# Modules.net
KiCad netlist of a schematic drawn in Altium Designer
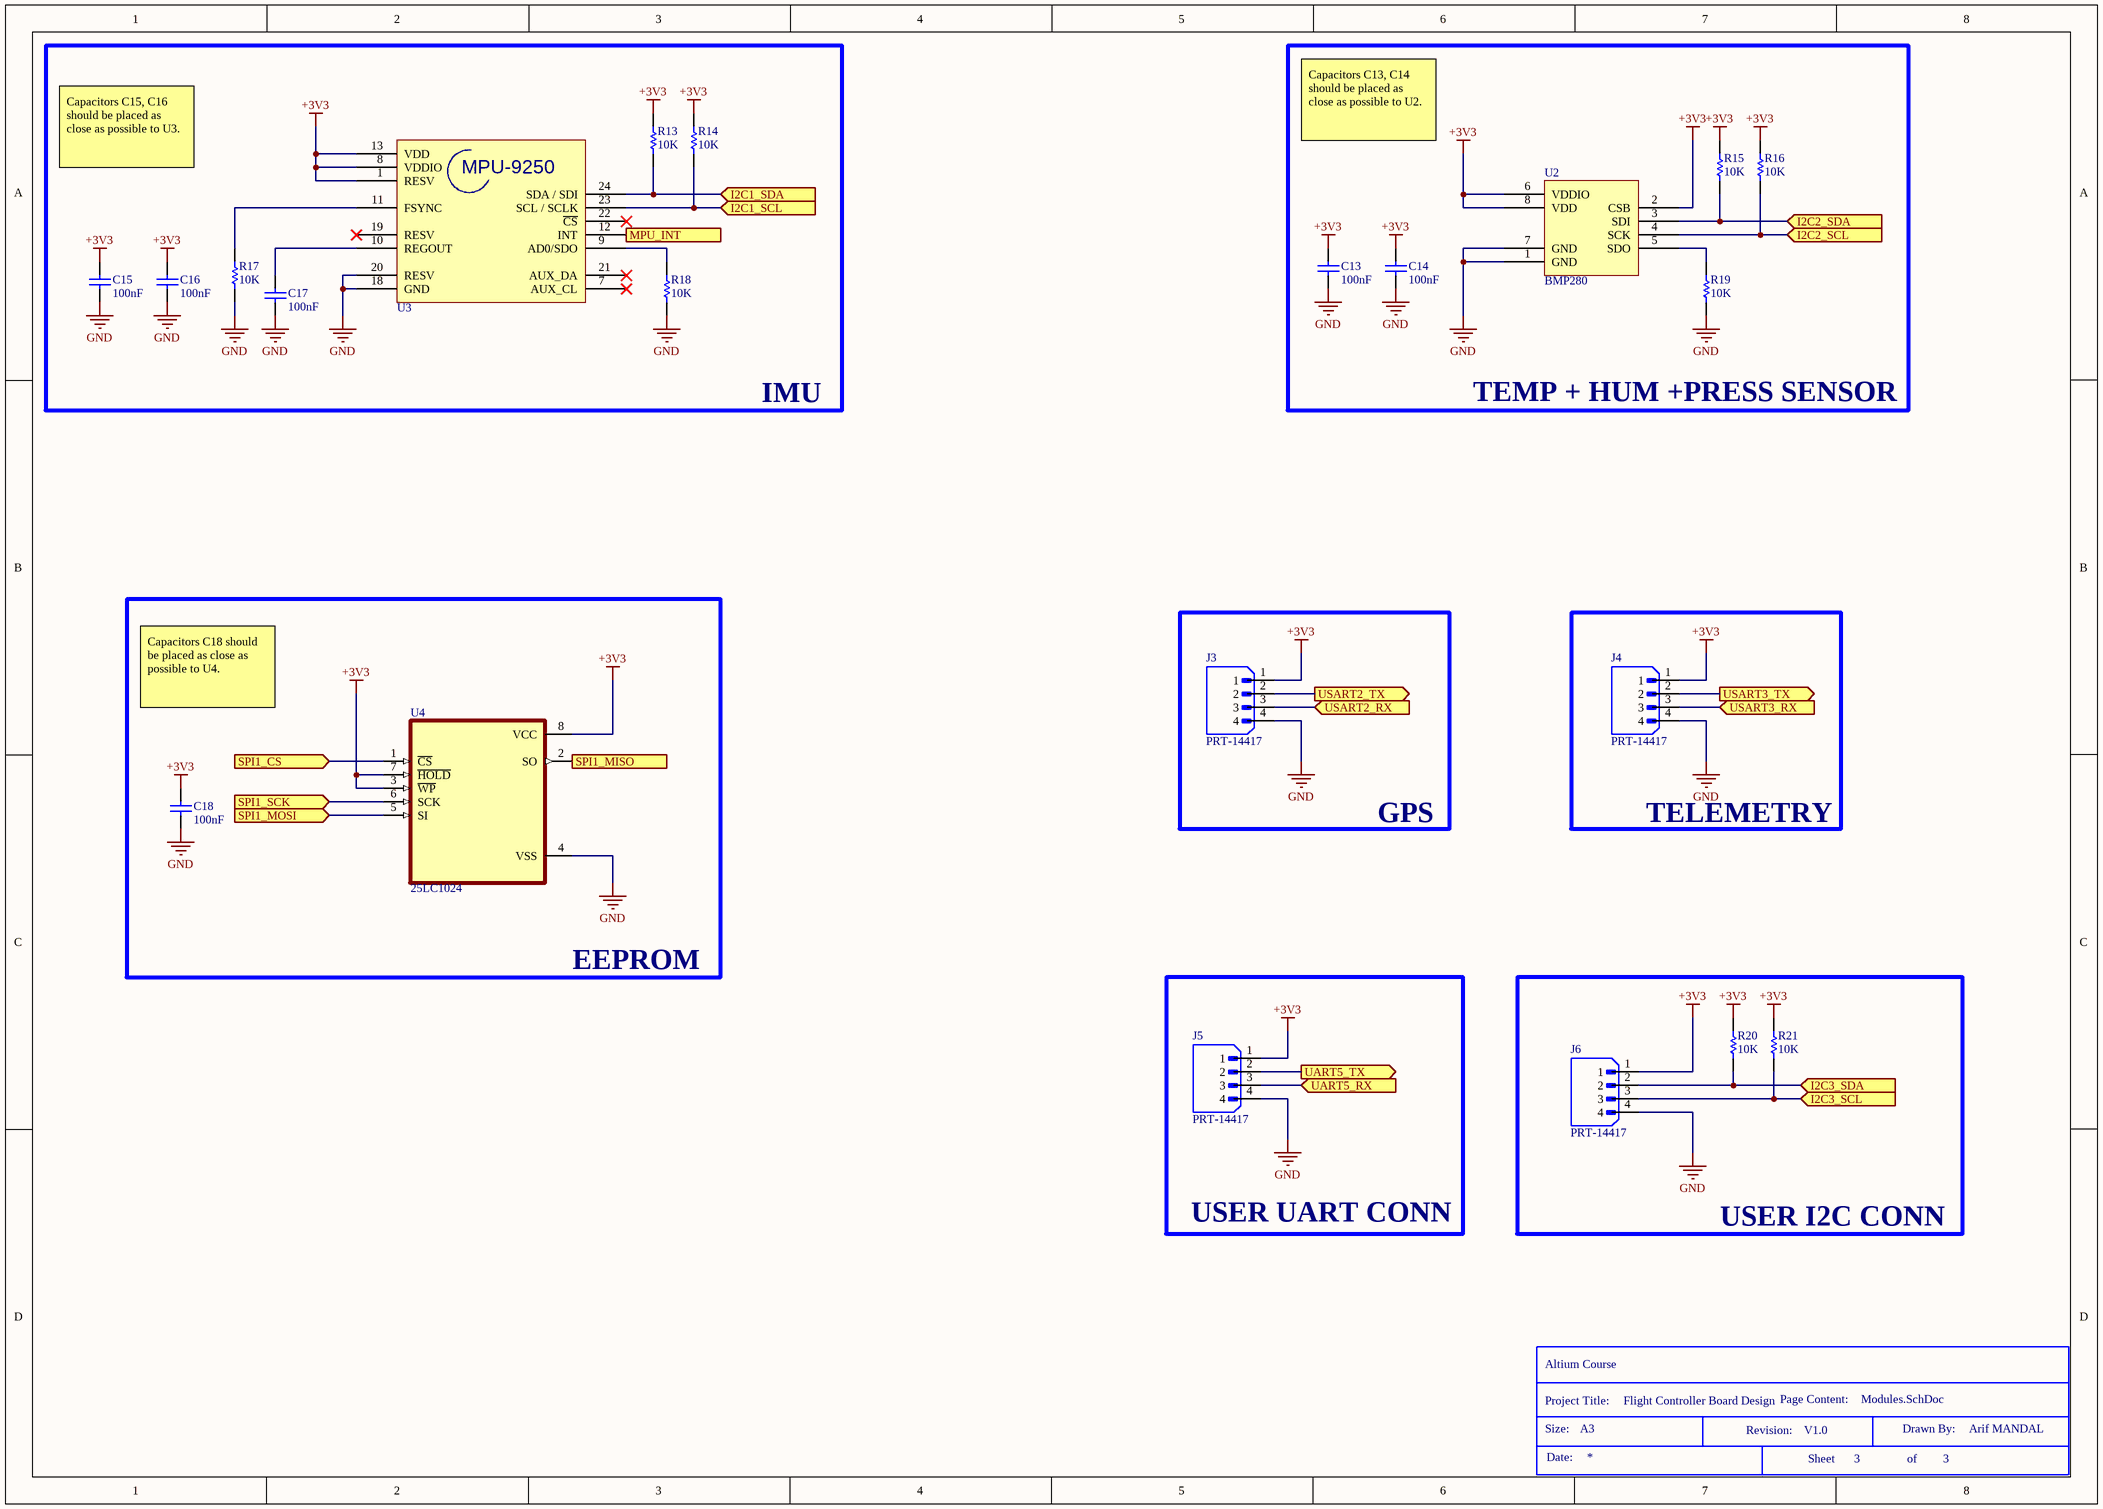
[diagram p0: Modules.SchDoc]

(export (version "E")
  (design (tool "Eeschema 10.0.6"))
  (components
    (comp (ref "C13")
      (value "100nF")
      (footprint "C805")
      (description "Capacitor")
      (fields (field (name "DESIGNER") "Parsa Malekpour"))
      (libsource (lib "ParsaLibrary") (part "Cap"))
    )
    (comp (ref "C14")
      (value "100nF")
      (footprint "C805")
      (description "Capacitor")
      (fields (field (name "DESIGNER") "Parsa Malekpour"))
      (libsource (lib "ParsaLibrary") (part "Cap"))
    )
    (comp (ref "C15")
      (value "100nF")
      (footprint "C805")
      (description "Capacitor")
      (fields (field (name "DESIGNER") "Parsa Malekpour"))
      (libsource (lib "ParsaLibrary") (part "Cap"))
    )
    (comp (ref "C16")
      (value "100nF")
      (footprint "C805")
      (description "Capacitor")
      (fields (field (name "DESIGNER") "Parsa Malekpour"))
      (libsource (lib "ParsaLibrary") (part "Cap"))
    )
    (comp (ref "C17")
      (value "100nF")
      (footprint "C805")
      (description "Capacitor")
      (fields (field (name "DESIGNER") "Parsa Malekpour"))
      (libsource (lib "ParsaLibrary") (part "Cap"))
    )
    (comp (ref "C18")
      (value "100nF")
      (footprint "C805")
      (description "Capacitor")
      (fields (field (name "DESIGNER") "Parsa Malekpour"))
      (libsource (lib "ParsaLibrary") (part "Cap"))
    )
    (comp (ref "J3")
      (value "PRT-14417")
      (footprint "SPARKFUN_PRT-14417")
      (description "QWIIC JST CONNECTOR - SMD 4-PIN")
      (fields (field (name "MF") "SparkFun Electronics"))
      (libsource (lib "Flight_Controller_Board_Design") (part "PRT-14417"))
    )
    (comp (ref "J4")
      (value "PRT-14417")
      (footprint "SPARKFUN_PRT-14417")
      (description "QWIIC JST CONNECTOR - SMD 4-PIN")
      (fields (field (name "MF") "SparkFun Electronics"))
      (libsource (lib "Flight_Controller_Board_Design") (part "PRT-14417"))
    )
    (comp (ref "J5")
      (value "PRT-14417")
      (footprint "SPARKFUN_PRT-14417")
      (description "QWIIC JST CONNECTOR - SMD 4-PIN")
      (fields (field (name "MF") "SparkFun Electronics"))
      (libsource (lib "Flight_Controller_Board_Design") (part "PRT-14417"))
    )
    (comp (ref "J6")
      (value "PRT-14417")
      (footprint "SPARKFUN_PRT-14417")
      (description "QWIIC JST CONNECTOR - SMD 4-PIN")
      (fields (field (name "MF") "SparkFun Electronics"))
      (libsource (lib "Flight_Controller_Board_Design") (part "PRT-14417"))
    )
    (comp (ref "R13")
      (value "10K")
      (footprint "R805")
      (description "Resistor")
      (fields (field (name "DESIGNER") "Parsa Malekpour"))
      (libsource (lib "ParsaLibrary") (part "Resistor"))
    )
    (comp (ref "R14")
      (value "10K")
      (footprint "R805")
      (description "Resistor")
      (fields (field (name "DESIGNER") "Parsa Malekpour"))
      (libsource (lib "ParsaLibrary") (part "Resistor"))
    )
    (comp (ref "R15")
      (value "10K")
      (footprint "R805")
      (description "Resistor")
      (fields (field (name "DESIGNER") "Parsa Malekpour"))
      (libsource (lib "ParsaLibrary") (part "Resistor"))
    )
    (comp (ref "R16")
      (value "10K")
      (footprint "R805")
      (description "Resistor")
      (fields (field (name "DESIGNER") "Parsa Malekpour"))
      (libsource (lib "ParsaLibrary") (part "Resistor"))
    )
    (comp (ref "R17")
      (value "10K")
      (footprint "R805")
      (description "Resistor")
      (fields (field (name "DESIGNER") "Parsa Malekpour"))
      (libsource (lib "ParsaLibrary") (part "Resistor"))
    )
    (comp (ref "R18")
      (value "10K")
      (footprint "R805")
      (description "Resistor")
      (fields (field (name "DESIGNER") "Parsa Malekpour"))
      (libsource (lib "ParsaLibrary") (part "Resistor"))
    )
    (comp (ref "R19")
      (value "10K")
      (footprint "R805")
      (description "Resistor")
      (fields (field (name "DESIGNER") "Parsa Malekpour"))
      (libsource (lib "ParsaLibrary") (part "Resistor"))
    )
    (comp (ref "R20")
      (value "10K")
      (footprint "R805")
      (description "Resistor")
      (fields (field (name "DESIGNER") "Parsa Malekpour"))
      (libsource (lib "ParsaLibrary") (part "Resistor"))
    )
    (comp (ref "R21")
      (value "10K")
      (footprint "R805")
      (description "Resistor")
      (fields (field (name "DESIGNER") "Parsa Malekpour"))
      (libsource (lib "ParsaLibrary") (part "Resistor"))
    )
    (comp (ref "U2")
      (value "BMP280")
      (footprint "BMP280")
      (description "Digital Pressure Sensor")
      (libsource (lib "ParsaLibrary") (part "BMP280"))
    )
    (comp (ref "U3")
      (value "MPU-9250")
      (footprint "QFN-24")
      (libsource (lib "ParsaLibrary") (part "MPU-9250"))
    )
    (comp (ref "U4")
      (value "25LC1024")
      (footprint "SOIC-8N")
      (description "EEPROM Memory IC 1Mb _128K x 8_ SPI 20MHz 8-SOIJ")
      (fields (field (name "MP") "25LC1024-I/SM") (field (name "MF") "Microchip"))
      (libsource (lib "Flight_Controller_Board_Design") (part "25LC1024"))
    )
  )
  (nets
    (net (code "1") (name "+3V3") (class "Default")
      (node (ref "C13") (pin "2") (pinfunction "2_2") (pintype "passive"))
      (node (ref "C14") (pin "2") (pinfunction "2_2") (pintype "passive"))
      (node (ref "C15") (pin "2") (pinfunction "2_2") (pintype "passive"))
      (node (ref "C16") (pin "2") (pinfunction "2_2") (pintype "passive"))
      (node (ref "C18") (pin "2") (pinfunction "2_2") (pintype "passive"))
      (node (ref "J3") (pin "1") (pinfunction "1_1") (pintype "passive"))
      (node (ref "J4") (pin "1") (pinfunction "1_1") (pintype "passive"))
      (node (ref "J5") (pin "1") (pinfunction "1_1") (pintype "passive"))
      (node (ref "J6") (pin "1") (pinfunction "1_1") (pintype "passive"))
      (node (ref "R13") (pin "2") (pinfunction "2_2") (pintype "passive"))
      (node (ref "R14") (pin "2") (pinfunction "2_2") (pintype "passive"))
      (node (ref "R15") (pin "2") (pinfunction "2_2") (pintype "passive"))
      (node (ref "R16") (pin "2") (pinfunction "2_2") (pintype "passive"))
      (node (ref "R20") (pin "2") (pinfunction "2_2") (pintype "passive"))
      (node (ref "R21") (pin "2") (pinfunction "2_2") (pintype "passive"))
      (node (ref "U2") (pin "2") (pinfunction "CSB_2") (pintype "passive"))
      (node (ref "U2") (pin "6") (pinfunction "VDDIO_6") (pintype "passive"))
      (node (ref "U2") (pin "8") (pinfunction "VDD_8") (pintype "passive"))
      (node (ref "U3") (pin "1") (pinfunction "RESV_1") (pintype "passive"))
      (node (ref "U3") (pin "13") (pinfunction "VDD_13") (pintype "passive"))
      (node (ref "U3") (pin "8") (pinfunction "VDDIO_8") (pintype "passive"))
      (node (ref "U4") (pin "3") (pinfunction "~{WP}_3") (pintype "input"))
      (node (ref "U4") (pin "7") (pinfunction "~{HOLD}_7") (pintype "input"))
      (node (ref "U4") (pin "8") (pinfunction "VCC_8") (pintype "power_in"))
    )
    (net (code "2") (name "/I2C1_SCL") (class "Default")
      (node (ref "R14") (pin "1") (pinfunction "1_1") (pintype "passive"))
      (node (ref "U3") (pin "23") (pinfunction "SCL_/_SCLK_23") (pintype "passive"))
    )
    (net (code "3") (name "/I2C1_SDA") (class "Default")
      (node (ref "R13") (pin "1") (pinfunction "1_1") (pintype "passive"))
      (node (ref "U3") (pin "24") (pinfunction "SDA_/_SDI_24") (pintype "passive"))
    )
    (net (code "4") (name "/I2C2_SCL") (class "Default")
      (node (ref "R16") (pin "1") (pinfunction "1_1") (pintype "passive"))
      (node (ref "U2") (pin "4") (pinfunction "SCK_4") (pintype "passive"))
    )
    (net (code "5") (name "/I2C2_SDA") (class "Default")
      (node (ref "R15") (pin "1") (pinfunction "1_1") (pintype "passive"))
      (node (ref "U2") (pin "3") (pinfunction "SDI_3") (pintype "passive"))
    )
    (net (code "6") (name "/I2C3_SCL") (class "Default")
      (node (ref "J6") (pin "3") (pinfunction "3_3") (pintype "passive"))
      (node (ref "R21") (pin "1") (pinfunction "1_1") (pintype "passive"))
    )
    (net (code "7") (name "/I2C3_SDA") (class "Default")
      (node (ref "J6") (pin "2") (pinfunction "2_2") (pintype "passive"))
      (node (ref "R20") (pin "1") (pinfunction "1_1") (pintype "passive"))
    )
    (net (code "8") (name "/MPU_INT") (class "Default")
      (node (ref "U3") (pin "12") (pinfunction "INT_12") (pintype "passive"))
    )
    (net (code "9") (name "/SPI1_CS") (class "Default")
      (node (ref "U4") (pin "1") (pinfunction "~{CS}_1") (pintype "input"))
    )
    (net (code "10") (name "/SPI1_MISO") (class "Default")
      (node (ref "U4") (pin "2") (pinfunction "SO_2") (pintype "output"))
    )
    (net (code "11") (name "/SPI1_MOSI") (class "Default")
      (node (ref "U4") (pin "5") (pinfunction "SI_5") (pintype "input"))
    )
    (net (code "12") (name "/SPI1_SCK") (class "Default")
      (node (ref "U4") (pin "6") (pinfunction "SCK_6") (pintype "input"))
    )
    (net (code "13") (name "/UART5_RX") (class "Default")
      (node (ref "J5") (pin "3") (pinfunction "3_3") (pintype "passive"))
    )
    (net (code "14") (name "/UART5_TX") (class "Default")
      (node (ref "J5") (pin "2") (pinfunction "2_2") (pintype "passive"))
    )
    (net (code "15") (name "/USART2_RX") (class "Default")
      (node (ref "J3") (pin "3") (pinfunction "3_3") (pintype "passive"))
    )
    (net (code "16") (name "/USART2_TX") (class "Default")
      (node (ref "J3") (pin "2") (pinfunction "2_2") (pintype "passive"))
    )
    (net (code "17") (name "/USART3_RX") (class "Default")
      (node (ref "J4") (pin "3") (pinfunction "3_3") (pintype "passive"))
    )
    (net (code "18") (name "/USART3_TX") (class "Default")
      (node (ref "J4") (pin "2") (pinfunction "2_2") (pintype "passive"))
    )
    (net (code "19") (name "GND") (class "Default")
      (node (ref "C13") (pin "1") (pinfunction "1_1") (pintype "passive"))
      (node (ref "C14") (pin "1") (pinfunction "1_1") (pintype "passive"))
      (node (ref "C15") (pin "1") (pinfunction "1_1") (pintype "passive"))
      (node (ref "C16") (pin "1") (pinfunction "1_1") (pintype "passive"))
      (node (ref "C17") (pin "1") (pinfunction "1_1") (pintype "passive"))
      (node (ref "C18") (pin "1") (pinfunction "1_1") (pintype "passive"))
      (node (ref "J3") (pin "4") (pinfunction "4_4") (pintype "passive"))
      (node (ref "J4") (pin "4") (pinfunction "4_4") (pintype "passive"))
      (node (ref "J5") (pin "4") (pinfunction "4_4") (pintype "passive"))
      (node (ref "J6") (pin "4") (pinfunction "4_4") (pintype "passive"))
      (node (ref "R17") (pin "1") (pinfunction "1_1") (pintype "passive"))
      (node (ref "R18") (pin "1") (pinfunction "1_1") (pintype "passive"))
      (node (ref "R19") (pin "1") (pinfunction "1_1") (pintype "passive"))
      (node (ref "U2") (pin "1") (pinfunction "GND_1") (pintype "passive"))
      (node (ref "U2") (pin "7") (pinfunction "GND_7") (pintype "passive"))
      (node (ref "U3") (pin "18") (pinfunction "GND_18") (pintype "passive"))
      (node (ref "U3") (pin "20") (pinfunction "RESV_20") (pintype "passive"))
      (node (ref "U4") (pin "4") (pinfunction "VSS_4") (pintype "power_in"))
    )
    (net (code "20") (name "Net-(U2-SDO)") (class "Default")
      (node (ref "R19") (pin "2") (pinfunction "2_2") (pintype "passive"))
      (node (ref "U2") (pin "5") (pinfunction "SDO_5") (pintype "passive"))
    )
    (net (code "21") (name "Net-(U3-AD0{slash}SDO)") (class "Default")
      (node (ref "R18") (pin "2") (pinfunction "2_2") (pintype "passive"))
      (node (ref "U3") (pin "9") (pinfunction "AD0/SDO_9") (pintype "passive"))
    )
    (net (code "22") (name "Net-(U3-FSYNC)") (class "Default")
      (node (ref "R17") (pin "2") (pinfunction "2_2") (pintype "passive"))
      (node (ref "U3") (pin "11") (pinfunction "FSYNC_11") (pintype "passive"))
    )
    (net (code "23") (name "Net-(U3-REGOUT)") (class "Default")
      (node (ref "C17") (pin "2") (pinfunction "2_2") (pintype "passive"))
      (node (ref "U3") (pin "10") (pinfunction "REGOUT_10") (pintype "passive"))
    )
    (net (code "24") (name "unconnected-(U3-AUX_CL-Pad7)") (class "Default")
      (node (ref "U3") (pin "7") (pinfunction "AUX_CL_7") (pintype "passive+no_connect"))
    )
    (net (code "25") (name "unconnected-(U3-AUX_DA-Pad21)") (class "Default")
      (node (ref "U3") (pin "21") (pinfunction "AUX_DA_21") (pintype "passive+no_connect"))
    )
    (net (code "26") (name "unconnected-(U3-RESV-Pad19)") (class "Default")
      (node (ref "U3") (pin "19") (pinfunction "RESV_19") (pintype "passive+no_connect"))
    )
    (net (code "27") (name "unconnected-(U3-~{CS}-Pad22)") (class "Default")
      (node (ref "U3") (pin "22") (pinfunction "~{CS}_22") (pintype "passive+no_connect"))
    )
  )
)
